# bus.net
KiCad netlist of a schematic drawn in EAGLE
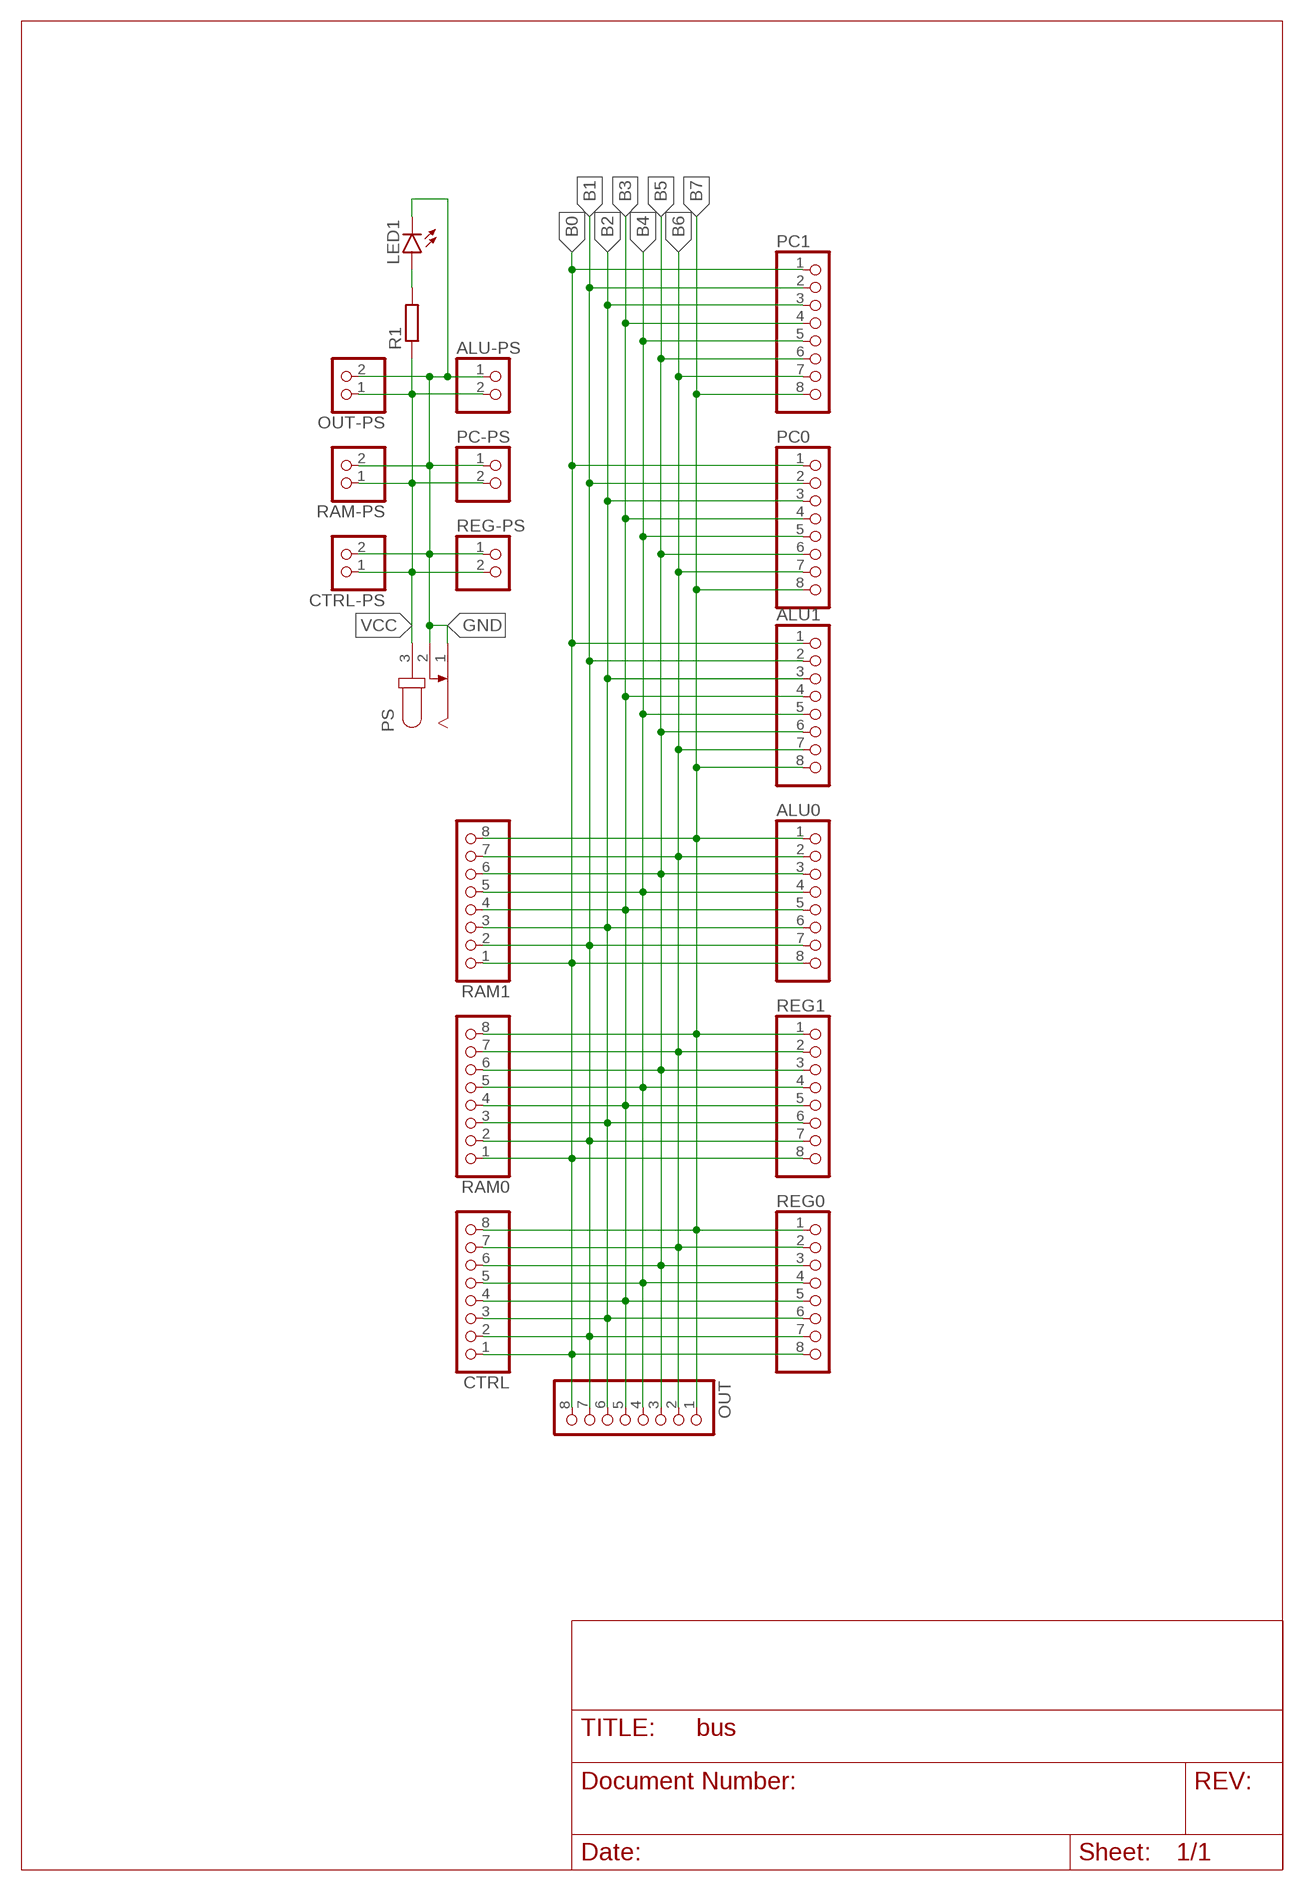
[diagram p0: schematic, sheet 1]

(export (version "E")
  (design (tool "Eeschema 10.0.6"))
  (components
    (comp (ref "ALU-PS")
      (value "PINHD-1X2")
      (footprint "eagle-import:1X02")
      (libsource (lib "eagle-import") (part "PINHD-1X2"))
    )
    (comp (ref "ALU0")
      (value "PINHD-1X8")
      (footprint "eagle-import:1X08")
      (libsource (lib "eagle-import") (part "PINHD-1X8"))
    )
    (comp (ref "ALU1")
      (value "PINHD-1X8")
      (footprint "eagle-import:1X08")
      (libsource (lib "eagle-import") (part "PINHD-1X8"))
    )
    (comp (ref "CTRL")
      (value "PINHD-1X8")
      (footprint "eagle-import:1X08")
      (libsource (lib "eagle-import") (part "PINHD-1X8"))
    )
    (comp (ref "CTRL-PS")
      (value "PINHD-1X2")
      (footprint "eagle-import:1X02")
      (libsource (lib "eagle-import") (part "PINHD-1X2"))
    )
    (comp (ref "LED1")
      (value "LED5MM")
      (footprint "eagle-import:LED5MM")
      (libsource (lib "eagle-import") (part "LED5MM"))
    )
    (comp (ref "OUT")
      (value "PINHD-1X8")
      (footprint "eagle-import:1X08")
      (libsource (lib "eagle-import") (part "PINHD-1X8"))
    )
    (comp (ref "OUT-PS")
      (value "PINHD-1X2")
      (footprint "eagle-import:1X02")
      (libsource (lib "eagle-import") (part "PINHD-1X2"))
    )
    (comp (ref "PC-PS")
      (value "PINHD-1X2")
      (footprint "eagle-import:1X02")
      (libsource (lib "eagle-import") (part "PINHD-1X2"))
    )
    (comp (ref "PC0")
      (value "PINHD-1X8")
      (footprint "eagle-import:1X08")
      (libsource (lib "eagle-import") (part "PINHD-1X8"))
    )
    (comp (ref "PC1")
      (value "PINHD-1X8")
      (footprint "eagle-import:1X08")
      (libsource (lib "eagle-import") (part "PINHD-1X8"))
    )
    (comp (ref "PS")
      (value "JACK-PLUG0")
      (footprint "eagle-import:SPC4077")
      (libsource (lib "eagle-import") (part "JACK-PLUG0"))
    )
    (comp (ref "R1")
      (value "R-EU_0204/7")
      (footprint "eagle-import:0204_7")
      (libsource (lib "eagle-import") (part "R-EU_0204/7"))
    )
    (comp (ref "RAM-PS")
      (value "PINHD-1X2")
      (footprint "eagle-import:1X02")
      (libsource (lib "eagle-import") (part "PINHD-1X2"))
    )
    (comp (ref "RAM0")
      (value "PINHD-1X8")
      (footprint "eagle-import:1X08")
      (libsource (lib "eagle-import") (part "PINHD-1X8"))
    )
    (comp (ref "RAM1")
      (value "PINHD-1X8")
      (footprint "eagle-import:1X08")
      (libsource (lib "eagle-import") (part "PINHD-1X8"))
    )
    (comp (ref "REG-PS")
      (value "PINHD-1X2")
      (footprint "eagle-import:1X02")
      (libsource (lib "eagle-import") (part "PINHD-1X2"))
    )
    (comp (ref "REG0")
      (value "PINHD-1X8")
      (footprint "eagle-import:1X08")
      (libsource (lib "eagle-import") (part "PINHD-1X8"))
    )
    (comp (ref "REG1")
      (value "PINHD-1X8")
      (footprint "eagle-import:1X08")
      (libsource (lib "eagle-import") (part "PINHD-1X8"))
    )
  )
  (nets
    (net (code "1") (name "B0") (class "Default")
      (node (ref "ALU0") (pin "8") (pinfunction "8_8") (pintype "passive"))
      (node (ref "ALU1") (pin "1") (pinfunction "1_1") (pintype "passive"))
      (node (ref "CTRL") (pin "1") (pinfunction "1_1") (pintype "passive"))
      (node (ref "OUT") (pin "8") (pinfunction "8_8") (pintype "passive"))
      (node (ref "PC0") (pin "1") (pinfunction "1_1") (pintype "passive"))
      (node (ref "PC1") (pin "1") (pinfunction "1_1") (pintype "passive"))
      (node (ref "RAM0") (pin "1") (pinfunction "1_1") (pintype "passive"))
      (node (ref "RAM1") (pin "1") (pinfunction "1_1") (pintype "passive"))
      (node (ref "REG0") (pin "8") (pinfunction "8_8") (pintype "passive"))
      (node (ref "REG1") (pin "8") (pinfunction "8_8") (pintype "passive"))
    )
    (net (code "2") (name "B1") (class "Default")
      (node (ref "ALU0") (pin "7") (pinfunction "7_7") (pintype "passive"))
      (node (ref "ALU1") (pin "2") (pinfunction "2_2") (pintype "passive"))
      (node (ref "CTRL") (pin "2") (pinfunction "2_2") (pintype "passive"))
      (node (ref "OUT") (pin "7") (pinfunction "7_7") (pintype "passive"))
      (node (ref "PC0") (pin "2") (pinfunction "2_2") (pintype "passive"))
      (node (ref "PC1") (pin "2") (pinfunction "2_2") (pintype "passive"))
      (node (ref "RAM0") (pin "2") (pinfunction "2_2") (pintype "passive"))
      (node (ref "RAM1") (pin "2") (pinfunction "2_2") (pintype "passive"))
      (node (ref "REG0") (pin "7") (pinfunction "7_7") (pintype "passive"))
      (node (ref "REG1") (pin "7") (pinfunction "7_7") (pintype "passive"))
    )
    (net (code "3") (name "B2") (class "Default")
      (node (ref "ALU0") (pin "6") (pinfunction "6_6") (pintype "passive"))
      (node (ref "ALU1") (pin "3") (pinfunction "3_3") (pintype "passive"))
      (node (ref "CTRL") (pin "3") (pinfunction "3_3") (pintype "passive"))
      (node (ref "OUT") (pin "6") (pinfunction "6_6") (pintype "passive"))
      (node (ref "PC0") (pin "3") (pinfunction "3_3") (pintype "passive"))
      (node (ref "PC1") (pin "3") (pinfunction "3_3") (pintype "passive"))
      (node (ref "RAM0") (pin "3") (pinfunction "3_3") (pintype "passive"))
      (node (ref "RAM1") (pin "3") (pinfunction "3_3") (pintype "passive"))
      (node (ref "REG0") (pin "6") (pinfunction "6_6") (pintype "passive"))
      (node (ref "REG1") (pin "6") (pinfunction "6_6") (pintype "passive"))
    )
    (net (code "4") (name "B3") (class "Default")
      (node (ref "ALU0") (pin "5") (pinfunction "5_5") (pintype "passive"))
      (node (ref "ALU1") (pin "4") (pinfunction "4_4") (pintype "passive"))
      (node (ref "CTRL") (pin "4") (pinfunction "4_4") (pintype "passive"))
      (node (ref "OUT") (pin "5") (pinfunction "5_5") (pintype "passive"))
      (node (ref "PC0") (pin "4") (pinfunction "4_4") (pintype "passive"))
      (node (ref "PC1") (pin "4") (pinfunction "4_4") (pintype "passive"))
      (node (ref "RAM0") (pin "4") (pinfunction "4_4") (pintype "passive"))
      (node (ref "RAM1") (pin "4") (pinfunction "4_4") (pintype "passive"))
      (node (ref "REG0") (pin "5") (pinfunction "5_5") (pintype "passive"))
      (node (ref "REG1") (pin "5") (pinfunction "5_5") (pintype "passive"))
    )
    (net (code "5") (name "B4") (class "Default")
      (node (ref "ALU0") (pin "4") (pinfunction "4_4") (pintype "passive"))
      (node (ref "ALU1") (pin "5") (pinfunction "5_5") (pintype "passive"))
      (node (ref "CTRL") (pin "5") (pinfunction "5_5") (pintype "passive"))
      (node (ref "OUT") (pin "4") (pinfunction "4_4") (pintype "passive"))
      (node (ref "PC0") (pin "5") (pinfunction "5_5") (pintype "passive"))
      (node (ref "PC1") (pin "5") (pinfunction "5_5") (pintype "passive"))
      (node (ref "RAM0") (pin "5") (pinfunction "5_5") (pintype "passive"))
      (node (ref "RAM1") (pin "5") (pinfunction "5_5") (pintype "passive"))
      (node (ref "REG0") (pin "4") (pinfunction "4_4") (pintype "passive"))
      (node (ref "REG1") (pin "4") (pinfunction "4_4") (pintype "passive"))
    )
    (net (code "6") (name "B5") (class "Default")
      (node (ref "ALU0") (pin "3") (pinfunction "3_3") (pintype "passive"))
      (node (ref "ALU1") (pin "6") (pinfunction "6_6") (pintype "passive"))
      (node (ref "CTRL") (pin "6") (pinfunction "6_6") (pintype "passive"))
      (node (ref "OUT") (pin "3") (pinfunction "3_3") (pintype "passive"))
      (node (ref "PC0") (pin "6") (pinfunction "6_6") (pintype "passive"))
      (node (ref "PC1") (pin "6") (pinfunction "6_6") (pintype "passive"))
      (node (ref "RAM0") (pin "6") (pinfunction "6_6") (pintype "passive"))
      (node (ref "RAM1") (pin "6") (pinfunction "6_6") (pintype "passive"))
      (node (ref "REG0") (pin "3") (pinfunction "3_3") (pintype "passive"))
      (node (ref "REG1") (pin "3") (pinfunction "3_3") (pintype "passive"))
    )
    (net (code "7") (name "B6") (class "Default")
      (node (ref "ALU0") (pin "2") (pinfunction "2_2") (pintype "passive"))
      (node (ref "ALU1") (pin "7") (pinfunction "7_7") (pintype "passive"))
      (node (ref "CTRL") (pin "7") (pinfunction "7_7") (pintype "passive"))
      (node (ref "OUT") (pin "2") (pinfunction "2_2") (pintype "passive"))
      (node (ref "PC0") (pin "7") (pinfunction "7_7") (pintype "passive"))
      (node (ref "PC1") (pin "7") (pinfunction "7_7") (pintype "passive"))
      (node (ref "RAM0") (pin "7") (pinfunction "7_7") (pintype "passive"))
      (node (ref "RAM1") (pin "7") (pinfunction "7_7") (pintype "passive"))
      (node (ref "REG0") (pin "2") (pinfunction "2_2") (pintype "passive"))
      (node (ref "REG1") (pin "2") (pinfunction "2_2") (pintype "passive"))
    )
    (net (code "8") (name "B7") (class "Default")
      (node (ref "ALU0") (pin "1") (pinfunction "1_1") (pintype "passive"))
      (node (ref "ALU1") (pin "8") (pinfunction "8_8") (pintype "passive"))
      (node (ref "CTRL") (pin "8") (pinfunction "8_8") (pintype "passive"))
      (node (ref "OUT") (pin "1") (pinfunction "1_1") (pintype "passive"))
      (node (ref "PC0") (pin "8") (pinfunction "8_8") (pintype "passive"))
      (node (ref "PC1") (pin "8") (pinfunction "8_8") (pintype "passive"))
      (node (ref "RAM0") (pin "8") (pinfunction "8_8") (pintype "passive"))
      (node (ref "RAM1") (pin "8") (pinfunction "8_8") (pintype "passive"))
      (node (ref "REG0") (pin "1") (pinfunction "1_1") (pintype "passive"))
      (node (ref "REG1") (pin "1") (pinfunction "1_1") (pintype "passive"))
    )
    (net (code "9") (name "GND") (class "Default")
      (node (ref "ALU-PS") (pin "1") (pinfunction "1_1") (pintype "passive"))
      (node (ref "CTRL-PS") (pin "2") (pinfunction "2_2") (pintype "passive"))
      (node (ref "LED1") (pin "K") (pinfunction "C_K") (pintype "passive"))
      (node (ref "OUT-PS") (pin "2") (pinfunction "2_2") (pintype "passive"))
      (node (ref "PC-PS") (pin "1") (pinfunction "1_1") (pintype "passive"))
      (node (ref "PS") (pin "1") (pinfunction "1_1") (pintype "passive"))
      (node (ref "PS") (pin "2") (pinfunction "2_2") (pintype "passive"))
      (node (ref "RAM-PS") (pin "2") (pinfunction "2_2") (pintype "passive"))
      (node (ref "REG-PS") (pin "1") (pinfunction "1_1") (pintype "passive"))
    )
    (net (code "10") (name "Net-(LED1-PadA)") (class "Default")
      (node (ref "LED1") (pin "A") (pinfunction "A_A") (pintype "passive"))
      (node (ref "R1") (pin "2") (pinfunction "2_2") (pintype "passive"))
    )
    (net (code "11") (name "VCC") (class "Default")
      (node (ref "ALU-PS") (pin "2") (pinfunction "2_2") (pintype "passive"))
      (node (ref "CTRL-PS") (pin "1") (pinfunction "1_1") (pintype "passive"))
      (node (ref "OUT-PS") (pin "1") (pinfunction "1_1") (pintype "passive"))
      (node (ref "PC-PS") (pin "2") (pinfunction "2_2") (pintype "passive"))
      (node (ref "PS") (pin "3") (pinfunction "3_3") (pintype "passive"))
      (node (ref "R1") (pin "1") (pinfunction "1_1") (pintype "passive"))
      (node (ref "RAM-PS") (pin "1") (pinfunction "1_1") (pintype "passive"))
      (node (ref "REG-PS") (pin "2") (pinfunction "2_2") (pintype "passive"))
    )
  )
)
